# ProDoc_pico-mac_v2_0.net
KiCad netlist of a schematic drawn in EasyEDA Pro
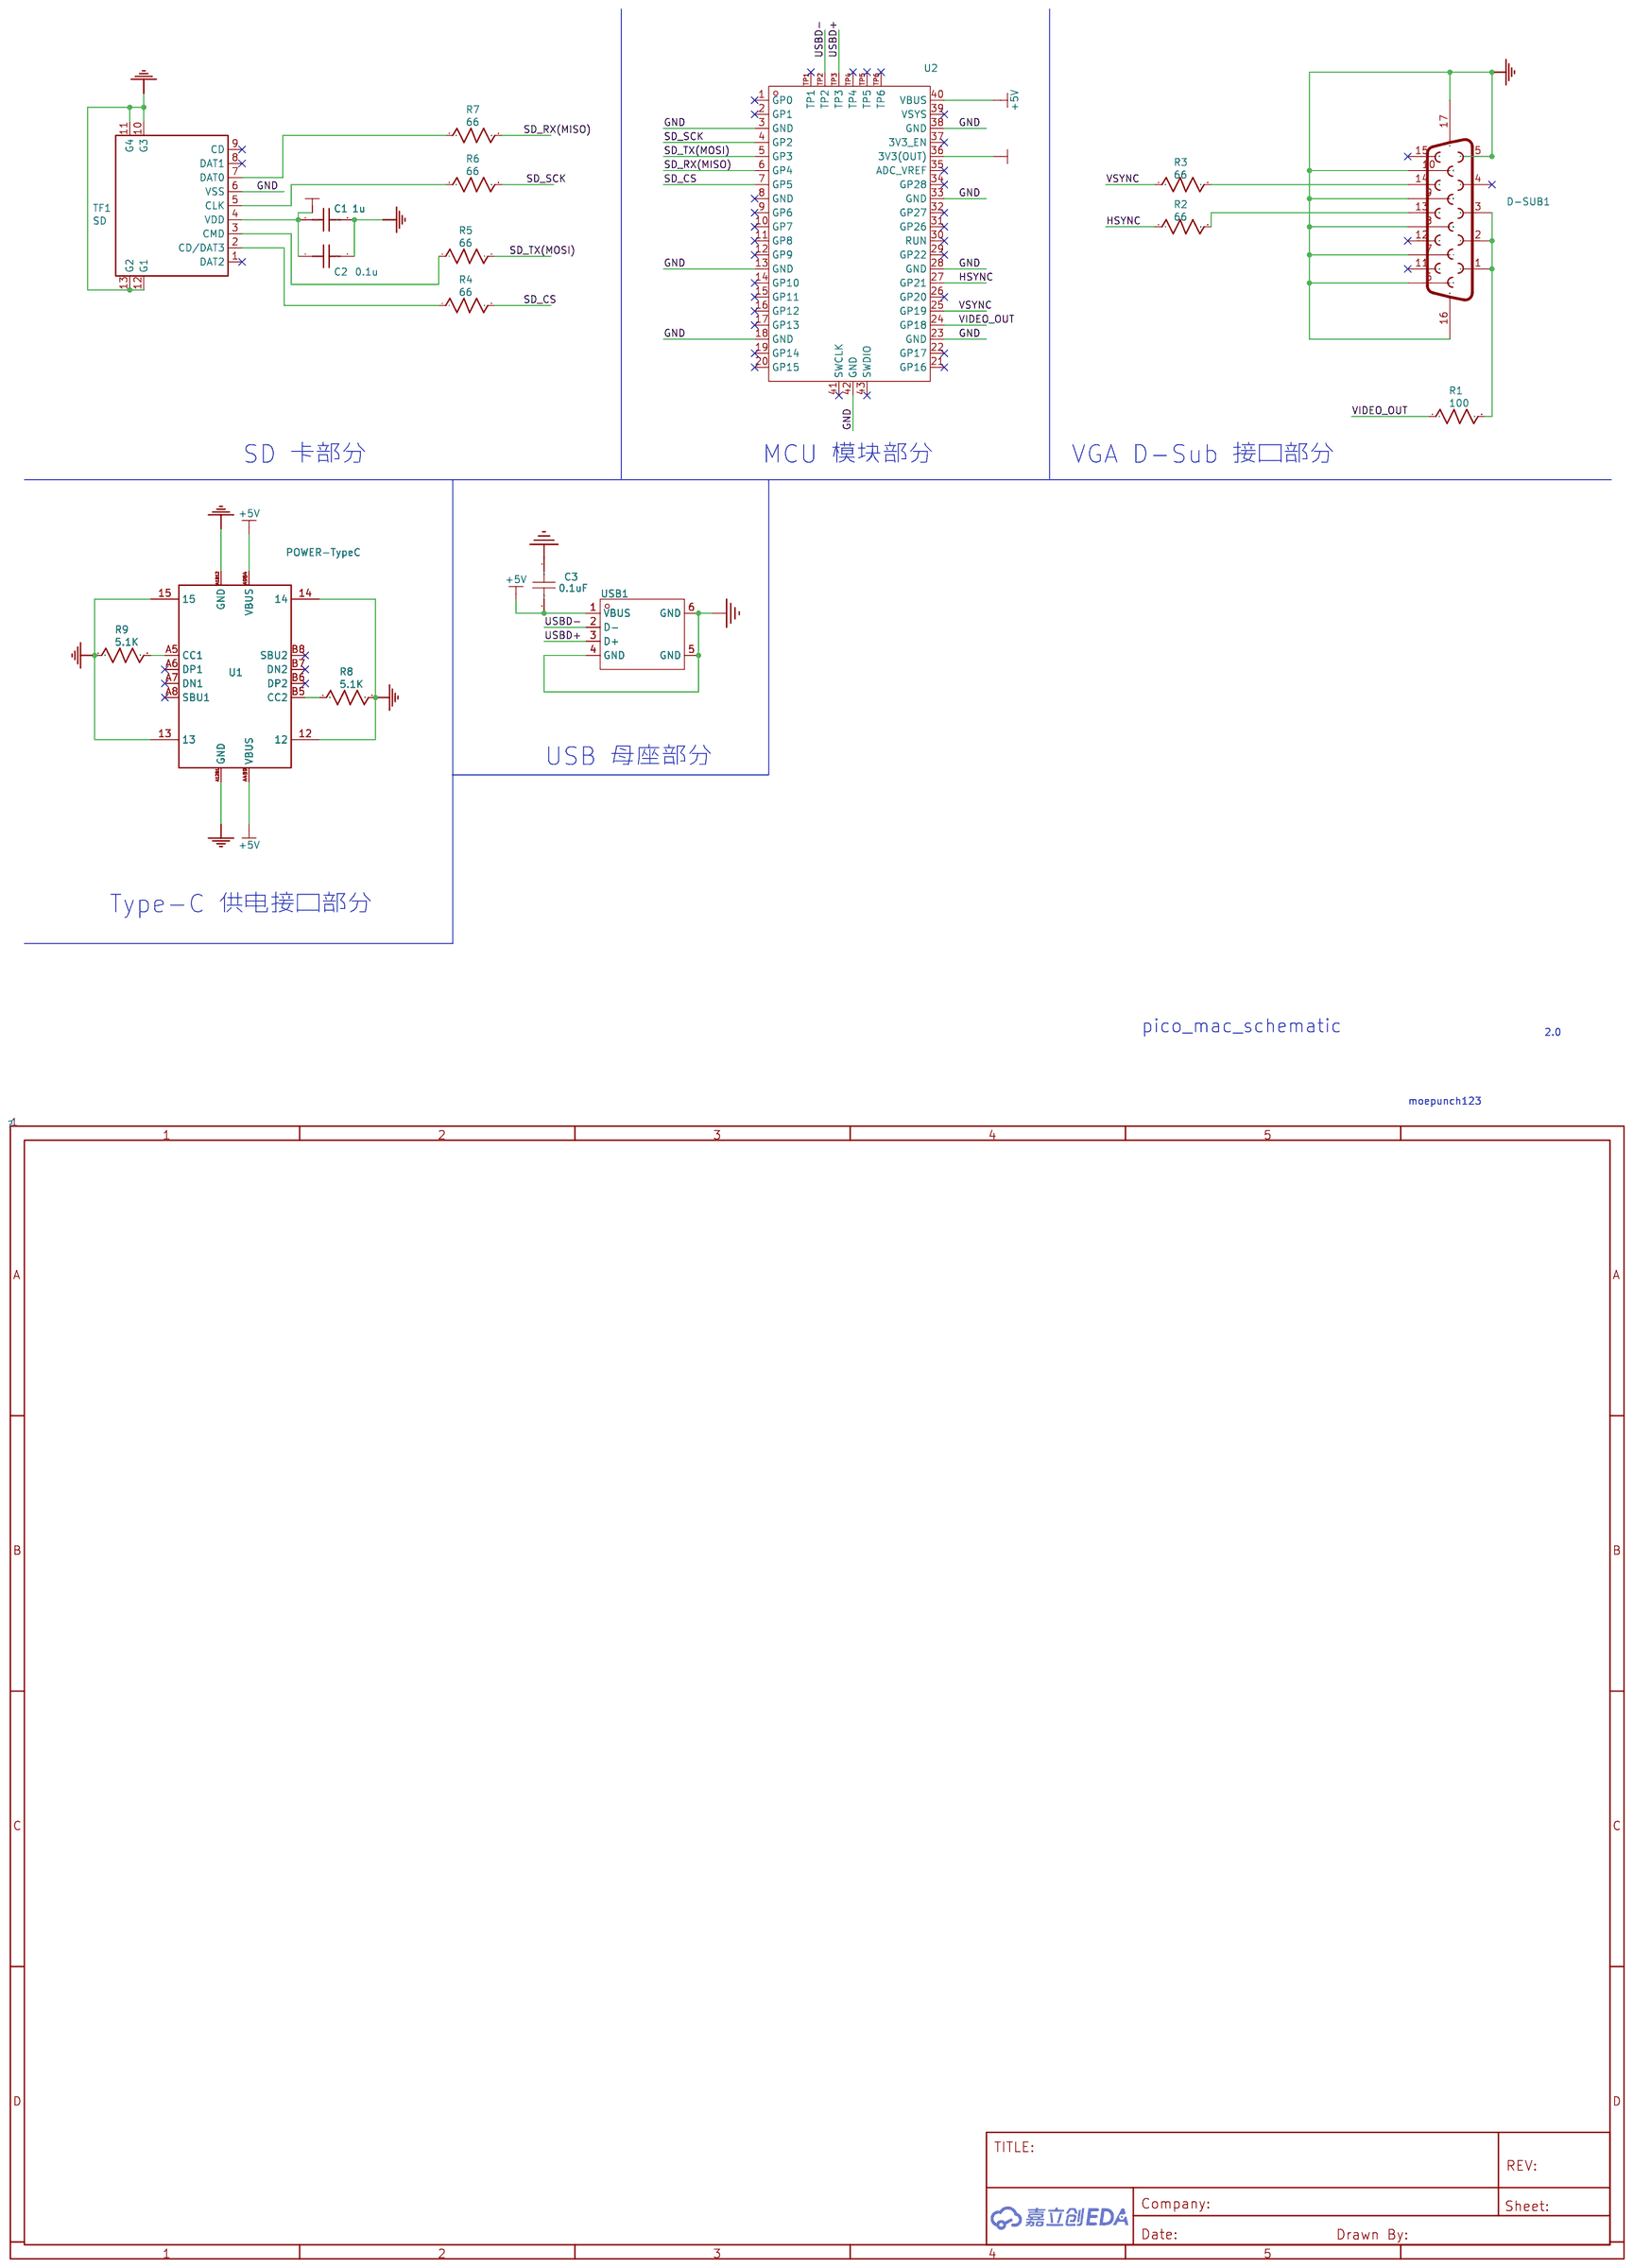
[diagram p0: schematic sheet]

(export (version "E")
  (design (tool "Eeschema 10.0.6"))
  (components
    (comp (ref "C1")
      (value "1u")
      (footprint "easyedapro:C0603")
      (fields (field (name "Contributor") "LCEDA_Lib"))
      (libsource (lib "easyedapro") (part "1u"))
    )
    (comp (ref "C2")
      (value "0.1u")
      (footprint "easyedapro:C0603")
      (fields (field (name "Contributor") "LCEDA_Lib"))
      (libsource (lib "easyedapro") (part "0.1u"))
    )
    (comp (ref "C3")
      (value "0.1uF")
      (footprint "easyedapro:C0603")
      (libsource (lib "easyedapro") (part "CapAcitance"))
    )
    (comp (ref "D-SUB1")
      (value "VGA")
      (footprint "easyedapro:DSUB-TH_KH-HDR15P-F3.08-VGA")
      (fields
        (field (name "Manufacturer Part") "KH-HDR15P-F3.08")
        (field (name "Manufacturer") "kinghelm(金航标)")
        (field (name "Contributor") "lcsc")
      )
      (libsource (lib "easyedapro") (part "VGA"))
    )
    (comp (ref "R1")
      (value "100")
      (footprint "easyedapro:R0603")
      (fields (field (name "Contributor") "LCEDA_Lib"))
      (libsource (lib "easyedapro") (part "100"))
    )
    (comp (ref "R2")
      (value "66")
      (footprint "easyedapro:R0603")
      (fields (field (name "Contributor") "LCEDA_Lib"))
      (libsource (lib "easyedapro") (part "66"))
    )
    (comp (ref "R3")
      (value "66")
      (footprint "easyedapro:R0603")
      (fields (field (name "Contributor") "LCEDA_Lib"))
      (libsource (lib "easyedapro") (part "66"))
    )
    (comp (ref "R4")
      (value "66")
      (footprint "easyedapro:R0603")
      (fields (field (name "Contributor") "LCEDA_Lib"))
      (libsource (lib "easyedapro") (part "66"))
    )
    (comp (ref "R5")
      (value "66")
      (footprint "easyedapro:R0603")
      (fields (field (name "Contributor") "LCEDA_Lib"))
      (libsource (lib "easyedapro") (part "66"))
    )
    (comp (ref "R6")
      (value "66")
      (footprint "easyedapro:R0603")
      (fields (field (name "Contributor") "LCEDA_Lib"))
      (libsource (lib "easyedapro") (part "66"))
    )
    (comp (ref "R7")
      (value "66")
      (footprint "easyedapro:R0603")
      (fields (field (name "Contributor") "LCEDA_Lib"))
      (libsource (lib "easyedapro") (part "66"))
    )
    (comp (ref "R8")
      (value "5.1K")
      (footprint "easyedapro:R0603")
      (fields (field (name "Contributor") "LCEDA_Lib"))
      (libsource (lib "easyedapro") (part "5.1K"))
    )
    (comp (ref "R9")
      (value "5.1K")
      (footprint "easyedapro:R0603")
      (fields (field (name "Contributor") "LCEDA_Lib"))
      (libsource (lib "easyedapro") (part "5.1K"))
    )
    (comp (ref "TF1")
      (value "SD")
      (footprint "easyedapro:TF-SMD_TF-15-15")
      (fields (field (name "Contributor") "lcsc"))
      (libsource (lib "easyedapro") (part "SD"))
    )
    (comp (ref "U1")
      (value "POWER-TypeC")
      (footprint "easyedapro:USB-C-SMD_HC-TYPE-C-16P-026W")
      (fields
        (field (name "Manufacturer Part") "HC-TYPE-C-16P-3M2S")
        (field (name "Manufacturer") "HC(虹成电子)")
        (field (name "Contributor") "lcsc")
      )
      (libsource (lib "easyedapro") (part "POWER-TypeC"))
    )
    (comp (ref "U2")
      (value "PICO")
      (footprint "easyedapro:COMM-SMD_L51.0-W21.0-P2.54_SC0916")
      (fields (field (name "Manufacturer") "Raspberry Pi(树莓派)"))
      (libsource (lib "easyedapro") (part "PICO"))
    )
    (comp (ref "USB1")
      (value "USB-231-ARY")
      (footprint "easyedapro:USB-A-TH_USB-231-ARY")
      (fields (field (name "Manufacturer") "XUNPU(讯普)"))
      (libsource (lib "easyedapro") (part "USB-231-ARY"))
    )
  )
  (nets
    (net (code "1") (name "+3.3V") (class "Default")
      (node (ref "C1") (pin "1") (pinfunction "1_1") (pintype "unspecified"))
      (node (ref "C2") (pin "1") (pinfunction "1_1") (pintype "unspecified"))
      (node (ref "TF1") (pin "4") (pinfunction "VDD_4") (pintype "unspecified"))
      (node (ref "U2") (pin "36") (pinfunction "3V3(OUT)_36") (pintype "unspecified"))
    )
    (net (code "2") (name "+5V") (class "Default")
      (node (ref "C3") (pin "2") (pinfunction "2_2") (pintype "input"))
      (node (ref "U1") (pin "A4B9") (pinfunction "VBUS_A4B9") (pintype "unspecified"))
      (node (ref "U1") (pin "A9B4") (pinfunction "VBUS_A9B4") (pintype "unspecified"))
      (node (ref "U2") (pin "40") (pinfunction "VBUS_40") (pintype "unspecified"))
      (node (ref "USB1") (pin "1") (pinfunction "VBUS_1") (pintype "unspecified"))
    )
    (net (code "3") (name "/HSYNC") (class "Default")
      (node (ref "R2") (pin "1") (pinfunction "1_1") (pintype "unspecified"))
      (node (ref "U2") (pin "27") (pinfunction "GP21_27") (pintype "unspecified"))
    )
    (net (code "4") (name "/SD_CS") (class "Default")
      (node (ref "R4") (pin "2") (pinfunction "2_2") (pintype "unspecified"))
      (node (ref "U2") (pin "7") (pinfunction "GP5_7") (pintype "unspecified"))
    )
    (net (code "5") (name "/SD_RX(MISO)") (class "Default")
      (node (ref "R7") (pin "2") (pinfunction "2_2") (pintype "unspecified"))
      (node (ref "U2") (pin "6") (pinfunction "GP4_6") (pintype "unspecified"))
    )
    (net (code "6") (name "/SD_SCK") (class "Default")
      (node (ref "R6") (pin "2") (pinfunction "2_2") (pintype "unspecified"))
      (node (ref "U2") (pin "4") (pinfunction "GP2_4") (pintype "unspecified"))
    )
    (net (code "7") (name "/SD_TX(MOSI)") (class "Default")
      (node (ref "R5") (pin "2") (pinfunction "2_2") (pintype "unspecified"))
      (node (ref "U2") (pin "5") (pinfunction "GP3_5") (pintype "unspecified"))
    )
    (net (code "8") (name "/USBD+") (class "Default")
      (node (ref "U2") (pin "TP3") (pinfunction "TP3_TP3") (pintype "unspecified"))
      (node (ref "USB1") (pin "3") (pinfunction "D+_3") (pintype "unspecified"))
    )
    (net (code "9") (name "/USBD-") (class "Default")
      (node (ref "U2") (pin "TP2") (pinfunction "TP2_TP2") (pintype "unspecified"))
      (node (ref "USB1") (pin "2") (pinfunction "D-_2") (pintype "unspecified"))
    )
    (net (code "10") (name "/VIDEO_OUT") (class "Default")
      (node (ref "R1") (pin "1") (pinfunction "1_1") (pintype "unspecified"))
      (node (ref "U2") (pin "24") (pinfunction "GP18_24") (pintype "unspecified"))
    )
    (net (code "11") (name "/VSYNC") (class "Default")
      (node (ref "R3") (pin "1") (pinfunction "1_1") (pintype "unspecified"))
      (node (ref "U2") (pin "25") (pinfunction "GP19_25") (pintype "unspecified"))
    )
    (net (code "12") (name "GND") (class "Default")
      (node (ref "C1") (pin "2") (pinfunction "2_2") (pintype "unspecified"))
      (node (ref "C2") (pin "2") (pinfunction "2_2") (pintype "unspecified"))
      (node (ref "C3") (pin "1") (pinfunction "1_1") (pintype "input"))
      (node (ref "D-SUB1") (pin "10") (pinfunction "10_10") (pintype "unspecified"))
      (node (ref "D-SUB1") (pin "16") (pinfunction "16_16") (pintype "unspecified"))
      (node (ref "D-SUB1") (pin "17") (pinfunction "17_17") (pintype "unspecified"))
      (node (ref "D-SUB1") (pin "5") (pinfunction "5_5") (pintype "unspecified"))
      (node (ref "D-SUB1") (pin "6") (pinfunction "6_6") (pintype "unspecified"))
      (node (ref "D-SUB1") (pin "7") (pinfunction "7_7") (pintype "unspecified"))
      (node (ref "D-SUB1") (pin "8") (pinfunction "8_8") (pintype "unspecified"))
      (node (ref "D-SUB1") (pin "9") (pinfunction "9_9") (pintype "unspecified"))
      (node (ref "R8") (pin "2") (pinfunction "2_2") (pintype "unspecified"))
      (node (ref "R9") (pin "1") (pinfunction "1_1") (pintype "unspecified"))
      (node (ref "TF1") (pin "10") (pinfunction "G3_10") (pintype "unspecified"))
      (node (ref "TF1") (pin "11") (pinfunction "G4_11") (pintype "unspecified"))
      (node (ref "TF1") (pin "12") (pinfunction "G1_12") (pintype "unspecified"))
      (node (ref "TF1") (pin "13") (pinfunction "G2_13") (pintype "unspecified"))
      (node (ref "TF1") (pin "6") (pinfunction "VSS_6") (pintype "unspecified"))
      (node (ref "U1") (pin "12") (pinfunction "12_12") (pintype "unspecified"))
      (node (ref "U1") (pin "13") (pinfunction "13_13") (pintype "unspecified"))
      (node (ref "U1") (pin "14") (pinfunction "14_14") (pintype "unspecified"))
      (node (ref "U1") (pin "15") (pinfunction "15_15") (pintype "unspecified"))
      (node (ref "U1") (pin "A12B1") (pinfunction "GND_A12B1") (pintype "unspecified"))
      (node (ref "U1") (pin "A1B12") (pinfunction "GND_A1B12") (pintype "unspecified"))
      (node (ref "U2") (pin "13") (pinfunction "GND_13") (pintype "unspecified"))
      (node (ref "U2") (pin "18") (pinfunction "GND_18") (pintype "unspecified"))
      (node (ref "U2") (pin "23") (pinfunction "GND_23") (pintype "unspecified"))
      (node (ref "U2") (pin "28") (pinfunction "GND_28") (pintype "unspecified"))
      (node (ref "U2") (pin "3") (pinfunction "GND_3") (pintype "unspecified"))
      (node (ref "U2") (pin "33") (pinfunction "GND_33") (pintype "unspecified"))
      (node (ref "U2") (pin "38") (pinfunction "GND_38") (pintype "unspecified"))
      (node (ref "U2") (pin "42") (pinfunction "GND_42") (pintype "unspecified"))
      (node (ref "USB1") (pin "4") (pinfunction "GND_4") (pintype "unspecified"))
      (node (ref "USB1") (pin "5") (pinfunction "GND_5") (pintype "unspecified"))
      (node (ref "USB1") (pin "6") (pinfunction "GND_6") (pintype "unspecified"))
    )
    (net (code "13") (name "Net-(D-SUB1-Pad1)") (class "Default")
      (node (ref "D-SUB1") (pin "1") (pinfunction "1_1") (pintype "unspecified"))
      (node (ref "D-SUB1") (pin "2") (pinfunction "2_2") (pintype "unspecified"))
      (node (ref "D-SUB1") (pin "3") (pinfunction "3_3") (pintype "unspecified"))
      (node (ref "R1") (pin "2") (pinfunction "2_2") (pintype "unspecified"))
    )
    (net (code "14") (name "Net-(D-SUB1-Pad13)") (class "Default")
      (node (ref "D-SUB1") (pin "13") (pinfunction "13_13") (pintype "unspecified"))
      (node (ref "R2") (pin "2") (pinfunction "2_2") (pintype "unspecified"))
    )
    (net (code "15") (name "Net-(D-SUB1-Pad14)") (class "Default")
      (node (ref "D-SUB1") (pin "14") (pinfunction "14_14") (pintype "unspecified"))
      (node (ref "R3") (pin "2") (pinfunction "2_2") (pintype "unspecified"))
    )
    (net (code "16") (name "Net-(TF1-CD{slash}DAT3)") (class "Default")
      (node (ref "R4") (pin "1") (pinfunction "1_1") (pintype "unspecified"))
      (node (ref "TF1") (pin "2") (pinfunction "CD/DAT3_2") (pintype "unspecified"))
    )
    (net (code "17") (name "Net-(TF1-CLK)") (class "Default")
      (node (ref "R6") (pin "1") (pinfunction "1_1") (pintype "unspecified"))
      (node (ref "TF1") (pin "5") (pinfunction "CLK_5") (pintype "unspecified"))
    )
    (net (code "18") (name "Net-(TF1-CMD)") (class "Default")
      (node (ref "R5") (pin "1") (pinfunction "1_1") (pintype "unspecified"))
      (node (ref "TF1") (pin "3") (pinfunction "CMD_3") (pintype "unspecified"))
    )
    (net (code "19") (name "Net-(TF1-DAT0)") (class "Default")
      (node (ref "R7") (pin "1") (pinfunction "1_1") (pintype "unspecified"))
      (node (ref "TF1") (pin "7") (pinfunction "DAT0_7") (pintype "unspecified"))
    )
    (net (code "20") (name "Net-(U1-CC1)") (class "Default")
      (node (ref "R9") (pin "2") (pinfunction "2_2") (pintype "unspecified"))
      (node (ref "U1") (pin "A5") (pinfunction "CC1_A5") (pintype "unspecified"))
    )
    (net (code "21") (name "Net-(U1-CC2)") (class "Default")
      (node (ref "R8") (pin "1") (pinfunction "1_1") (pintype "unspecified"))
      (node (ref "U1") (pin "B5") (pinfunction "CC2_B5") (pintype "unspecified"))
    )
    (net (code "22") (name "unconnected-(D-SUB1-Pad4)") (class "Default")
      (node (ref "D-SUB1") (pin "4") (pinfunction "4_4") (pintype "unspecified+no_connect"))
    )
    (net (code "23") (name "unconnected-(D-SUB1-Pad11)") (class "Default")
      (node (ref "D-SUB1") (pin "11") (pinfunction "11_11") (pintype "unspecified+no_connect"))
    )
    (net (code "24") (name "unconnected-(D-SUB1-Pad12)") (class "Default")
      (node (ref "D-SUB1") (pin "12") (pinfunction "12_12") (pintype "unspecified+no_connect"))
    )
    (net (code "25") (name "unconnected-(D-SUB1-Pad15)") (class "Default")
      (node (ref "D-SUB1") (pin "15") (pinfunction "15_15") (pintype "unspecified+no_connect"))
    )
    (net (code "26") (name "unconnected-(TF1-CD-Pad9)") (class "Default")
      (node (ref "TF1") (pin "9") (pinfunction "CD_9") (pintype "unspecified+no_connect"))
    )
    (net (code "27") (name "unconnected-(TF1-DAT1-Pad8)") (class "Default")
      (node (ref "TF1") (pin "8") (pinfunction "DAT1_8") (pintype "unspecified+no_connect"))
    )
    (net (code "28") (name "unconnected-(TF1-DAT2-Pad1)") (class "Default")
      (node (ref "TF1") (pin "1") (pinfunction "DAT2_1") (pintype "unspecified+no_connect"))
    )
    (net (code "29") (name "unconnected-(U1-DN1-PadA7)") (class "Default")
      (node (ref "U1") (pin "A7") (pinfunction "DN1_A7") (pintype "unspecified+no_connect"))
    )
    (net (code "30") (name "unconnected-(U1-DN2-PadB7)") (class "Default")
      (node (ref "U1") (pin "B7") (pinfunction "DN2_B7") (pintype "unspecified+no_connect"))
    )
    (net (code "31") (name "unconnected-(U1-DP1-PadA6)") (class "Default")
      (node (ref "U1") (pin "A6") (pinfunction "DP1_A6") (pintype "unspecified+no_connect"))
    )
    (net (code "32") (name "unconnected-(U1-DP2-PadB6)") (class "Default")
      (node (ref "U1") (pin "B6") (pinfunction "DP2_B6") (pintype "unspecified+no_connect"))
    )
    (net (code "33") (name "unconnected-(U1-SBU1-PadA8)") (class "Default")
      (node (ref "U1") (pin "A8") (pinfunction "SBU1_A8") (pintype "unspecified+no_connect"))
    )
    (net (code "34") (name "unconnected-(U1-SBU2-PadB8)") (class "Default")
      (node (ref "U1") (pin "B8") (pinfunction "SBU2_B8") (pintype "unspecified+no_connect"))
    )
    (net (code "35") (name "unconnected-(U2-3V3_EN-Pad37)") (class "Default")
      (node (ref "U2") (pin "37") (pinfunction "3V3_EN_37") (pintype "unspecified+no_connect"))
    )
    (net (code "36") (name "unconnected-(U2-ADC_VREF-Pad35)") (class "Default")
      (node (ref "U2") (pin "35") (pinfunction "ADC_VREF_35") (pintype "unspecified+no_connect"))
    )
    (net (code "37") (name "unconnected-(U2-GND-Pad8)") (class "Default")
      (node (ref "U2") (pin "8") (pinfunction "GND_8") (pintype "unspecified+no_connect"))
    )
    (net (code "38") (name "unconnected-(U2-GP0-Pad1)") (class "Default")
      (node (ref "U2") (pin "1") (pinfunction "GP0_1") (pintype "unspecified+no_connect"))
    )
    (net (code "39") (name "unconnected-(U2-GP1-Pad2)") (class "Default")
      (node (ref "U2") (pin "2") (pinfunction "GP1_2") (pintype "unspecified+no_connect"))
    )
    (net (code "40") (name "unconnected-(U2-GP6-Pad9)") (class "Default")
      (node (ref "U2") (pin "9") (pinfunction "GP6_9") (pintype "unspecified+no_connect"))
    )
    (net (code "41") (name "unconnected-(U2-GP7-Pad10)") (class "Default")
      (node (ref "U2") (pin "10") (pinfunction "GP7_10") (pintype "unspecified+no_connect"))
    )
    (net (code "42") (name "unconnected-(U2-GP8-Pad11)") (class "Default")
      (node (ref "U2") (pin "11") (pinfunction "GP8_11") (pintype "unspecified+no_connect"))
    )
    (net (code "43") (name "unconnected-(U2-GP9-Pad12)") (class "Default")
      (node (ref "U2") (pin "12") (pinfunction "GP9_12") (pintype "unspecified+no_connect"))
    )
    (net (code "44") (name "unconnected-(U2-GP10-Pad14)") (class "Default")
      (node (ref "U2") (pin "14") (pinfunction "GP10_14") (pintype "unspecified+no_connect"))
    )
    (net (code "45") (name "unconnected-(U2-GP11-Pad15)") (class "Default")
      (node (ref "U2") (pin "15") (pinfunction "GP11_15") (pintype "unspecified+no_connect"))
    )
    (net (code "46") (name "unconnected-(U2-GP12-Pad16)") (class "Default")
      (node (ref "U2") (pin "16") (pinfunction "GP12_16") (pintype "unspecified+no_connect"))
    )
    (net (code "47") (name "unconnected-(U2-GP13-Pad17)") (class "Default")
      (node (ref "U2") (pin "17") (pinfunction "GP13_17") (pintype "unspecified+no_connect"))
    )
    (net (code "48") (name "unconnected-(U2-GP14-Pad19)") (class "Default")
      (node (ref "U2") (pin "19") (pinfunction "GP14_19") (pintype "unspecified+no_connect"))
    )
    (net (code "49") (name "unconnected-(U2-GP15-Pad20)") (class "Default")
      (node (ref "U2") (pin "20") (pinfunction "GP15_20") (pintype "unspecified+no_connect"))
    )
    (net (code "50") (name "unconnected-(U2-GP16-Pad21)") (class "Default")
      (node (ref "U2") (pin "21") (pinfunction "GP16_21") (pintype "unspecified+no_connect"))
    )
    (net (code "51") (name "unconnected-(U2-GP17-Pad22)") (class "Default")
      (node (ref "U2") (pin "22") (pinfunction "GP17_22") (pintype "unspecified+no_connect"))
    )
    (net (code "52") (name "unconnected-(U2-GP20-Pad26)") (class "Default")
      (node (ref "U2") (pin "26") (pinfunction "GP20_26") (pintype "unspecified+no_connect"))
    )
    (net (code "53") (name "unconnected-(U2-GP22-Pad29)") (class "Default")
      (node (ref "U2") (pin "29") (pinfunction "GP22_29") (pintype "unspecified+no_connect"))
    )
    (net (code "54") (name "unconnected-(U2-GP26-Pad31)") (class "Default")
      (node (ref "U2") (pin "31") (pinfunction "GP26_31") (pintype "unspecified+no_connect"))
    )
    (net (code "55") (name "unconnected-(U2-GP27-Pad32)") (class "Default")
      (node (ref "U2") (pin "32") (pinfunction "GP27_32") (pintype "unspecified+no_connect"))
    )
    (net (code "56") (name "unconnected-(U2-GP28-Pad34)") (class "Default")
      (node (ref "U2") (pin "34") (pinfunction "GP28_34") (pintype "unspecified+no_connect"))
    )
    (net (code "57") (name "unconnected-(U2-PadTP1)") (class "Default")
      (node (ref "U2") (pin "TP1") (pinfunction "TP1_TP1") (pintype "unspecified+no_connect"))
    )
    (net (code "58") (name "unconnected-(U2-PadTP4)") (class "Default")
      (node (ref "U2") (pin "TP4") (pinfunction "TP4_TP4") (pintype "unspecified+no_connect"))
    )
    (net (code "59") (name "unconnected-(U2-PadTP5)") (class "Default")
      (node (ref "U2") (pin "TP5") (pinfunction "TP5_TP5") (pintype "unspecified+no_connect"))
    )
    (net (code "60") (name "unconnected-(U2-PadTP6)") (class "Default")
      (node (ref "U2") (pin "TP6") (pinfunction "TP6_TP6") (pintype "unspecified+no_connect"))
    )
    (net (code "61") (name "unconnected-(U2-RUN-Pad30)") (class "Default")
      (node (ref "U2") (pin "30") (pinfunction "RUN_30") (pintype "unspecified+no_connect"))
    )
    (net (code "62") (name "unconnected-(U2-SWCLK-Pad41)") (class "Default")
      (node (ref "U2") (pin "41") (pinfunction "SWCLK_41") (pintype "unspecified+no_connect"))
    )
    (net (code "63") (name "unconnected-(U2-SWDIO-Pad43)") (class "Default")
      (node (ref "U2") (pin "43") (pinfunction "SWDIO_43") (pintype "unspecified+no_connect"))
    )
    (net (code "64") (name "unconnected-(U2-VSYS-Pad39)") (class "Default")
      (node (ref "U2") (pin "39") (pinfunction "VSYS_39") (pintype "unspecified+no_connect"))
    )
  )
)
